# Sheet1.net
KiCad netlist of a schematic drawn in Altium Designer
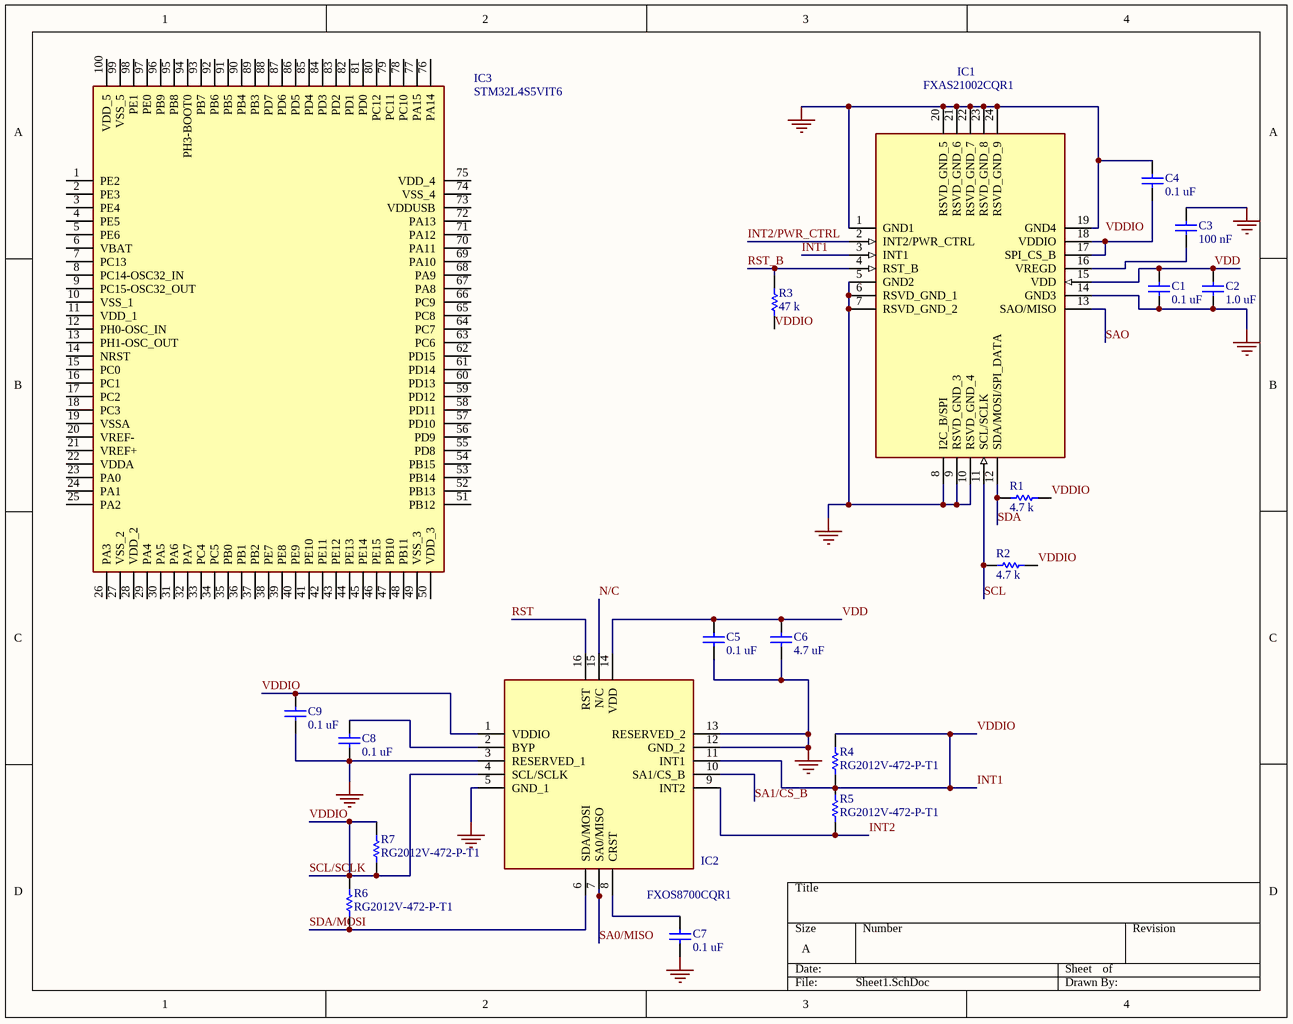
[diagram p0: Sheet1.SchDoc]

(export (version "E")
  (design (tool "Eeschema 10.0.6"))
  (components
    (comp (ref "C1")
      (value "0.1 uF")
      (footprint "CAPC1005X55X30ML05T10")
      (fields (field (name "MANUFACTURER") "Kemet") (field (name "PART NUMBER") "C0402C104J4RACTU"))
      (libsource (lib "Altium Content Vault") (part "CAP"))
    )
    (comp (ref "C2")
      (value "1.0 uF")
      (footprint "CAPC1005X55X30ML05T10")
      (fields (field (name "MANUFACTURER") "Kemet") (field (name "PART NUMBER") "C0402C104J4RACTU"))
      (libsource (lib "Altium Content Vault") (part "CAP"))
    )
    (comp (ref "C3")
      (value "100 nF")
      (footprint "CAPC1005X55X30ML05T10")
      (fields (field (name "MANUFACTURER") "Kemet") (field (name "PART NUMBER") "C0402C104J4RACTU"))
      (libsource (lib "Altium Content Vault") (part "CAP"))
    )
    (comp (ref "C4")
      (value "0.1 uF")
      (footprint "CAPC1005X55X30ML05T10")
      (fields (field (name "MANUFACTURER") "Kemet") (field (name "PART NUMBER") "C0402C104J4RACTU"))
      (libsource (lib "Altium Content Vault") (part "CAP"))
    )
    (comp (ref "C5")
      (value "0.1 uF")
      (footprint "CAPC1005X55X30ML05T10")
      (fields (field (name "MANUFACTURER") "Kemet") (field (name "PART NUMBER") "C0402C104J4RACTU"))
      (libsource (lib "Altium Content Vault") (part "CAP"))
    )
    (comp (ref "C6")
      (value "4.7 uF")
      (footprint "CAPC1005X55X30ML05T10")
      (fields (field (name "MANUFACTURER") "Kemet") (field (name "PART NUMBER") "C0402C104J4RACTU"))
      (libsource (lib "Altium Content Vault") (part "CAP"))
    )
    (comp (ref "C7")
      (value "0.1 uF")
      (footprint "CAPC1005X55X30ML05T10")
      (fields (field (name "MANUFACTURER") "Kemet") (field (name "PART NUMBER") "C0402C104J4RACTU"))
      (libsource (lib "Altium Content Vault") (part "CAP"))
    )
    (comp (ref "C8")
      (value "0.1 uF")
      (footprint "CAPC1005X55X30ML05T10")
      (fields (field (name "MANUFACTURER") "Kemet") (field (name "PART NUMBER") "C0402C104J4RACTU"))
      (libsource (lib "Altium Content Vault") (part "CAP"))
    )
    (comp (ref "C9")
      (value "0.1 uF")
      (footprint "CAPC1005X55X30ML05T10")
      (fields (field (name "MANUFACTURER") "Kemet") (field (name "PART NUMBER") "C0402C104J4RACTU"))
      (libsource (lib "Altium Content Vault") (part "CAP"))
    )
    (comp (ref "IC1")
      (value "FXAS21002CQR1")
      (footprint "SamacSys:FXAS21002CQR1")
      (description "Integrated Circuit")
      (fields (field (name "MOUSER PART NUMBER") "841-FXAS21002CQR1"))
      (libsource (lib "*") (part "FXAS21002CQR1"))
    )
    (comp (ref "IC2")
      (value "FXOS8700CQR1")
      (footprint "SamacSys:MMA8452QT")
      (description "Accelerometer")
      (fields (field (name "MOUSER PART NUMBER") "841-FXOS8700CQR1"))
      (libsource (lib "*") (part "FXOS8700CQR1"))
    )
    (comp (ref "IC3")
      (value "STM32L4S5VIT6")
      (footprint "SamacSys:QFP50P1600X1600X160-100N")
      (description "Integrated Circuit")
      (fields
        (field (name "MOUSER PART NUMBER") "511-STM32L4S5VIT6")
        (field (name "RS PART NUMBER") "1750803P")
      )
      (libsource (lib "*") (part "STM32L4S5VIT6"))
    )
    (comp (ref "R1")
      (value "4.7 k")
      (footprint "RESC2013X50X40LL20T20")
      (fields (field (name "PART NUMBER") "RG2012V-472-P-T1") (field (name "MANUFACTURER") "Susumu"))
      (libsource (lib "Altium Content Vault") (part "RES"))
    )
    (comp (ref "R2")
      (value "4.7 k")
      (footprint "RESC2013X50X40LL20T20")
      (fields (field (name "PART NUMBER") "RG2012V-472-P-T1") (field (name "MANUFACTURER") "Susumu"))
      (libsource (lib "Altium Content Vault") (part "RES"))
    )
    (comp (ref "R3")
      (value "47 k")
      (footprint "RESC2013X50X40ML20T20")
      (fields (field (name "PART NUMBER") "RG2012P-473-B-T5") (field (name "MANUFACTURER") "Susumu"))
      (libsource (lib "Altium Content Vault") (part "RES"))
    )
    (comp (ref "R4")
      (value "RG2012V-472-P-T1")
      (footprint "RESC2013X50X40LL20T20")
      (fields (field (name "MANUFACTURER") "Susumu"))
      (libsource (lib "Altium Content Vault") (part "RES"))
    )
    (comp (ref "R5")
      (value "RG2012V-472-P-T1")
      (footprint "RESC2013X50X40LL20T20")
      (fields (field (name "MANUFACTURER") "Susumu"))
      (libsource (lib "Altium Content Vault") (part "RES"))
    )
    (comp (ref "R6")
      (value "RG2012V-472-P-T1")
      (footprint "RESC2013X50X40LL20T20")
      (fields (field (name "MANUFACTURER") "Susumu"))
      (libsource (lib "Altium Content Vault") (part "RES"))
    )
    (comp (ref "R7")
      (value "RG2012V-472-P-T1")
      (footprint "RESC2013X50X40LL20T20")
      (fields (field (name "MANUFACTURER") "Susumu"))
      (libsource (lib "Altium Content Vault") (part "RES"))
    )
  )
  (nets
    (net (code "1") (name "/INT1") (class "Default")
      (node (ref "C9") (pin "2") (pinfunction "2_2") (pintype "passive"))
      (node (ref "IC1") (pin "3") (pinfunction "INT1_3") (pintype "input"))
      (node (ref "IC2") (pin "1") (pinfunction "VDDIO_1") (pintype "passive"))
      (node (ref "IC2") (pin "11") (pinfunction "INT1_11") (pintype "passive"))
      (node (ref "IC2") (pin "4") (pinfunction "SCL/SCLK_4") (pintype "passive"))
      (node (ref "R1") (pin "2") (pinfunction "2_2") (pintype "passive"))
      (node (ref "R2") (pin "2") (pinfunction "2_2") (pintype "passive"))
      (node (ref "R3") (pin "1") (pinfunction "1_1") (pintype "passive"))
      (node (ref "R4") (pin "1") (pinfunction "1_1") (pintype "passive"))
      (node (ref "R4") (pin "2") (pinfunction "2_2") (pintype "passive"))
      (node (ref "R6") (pin "2") (pinfunction "2_2") (pintype "passive"))
      (node (ref "R7") (pin "1") (pinfunction "1_1") (pintype "passive"))
      (node (ref "R7") (pin "2") (pinfunction "2_2") (pintype "passive"))
    )
    (net (code "2") (name "/INT2") (class "Default")
      (node (ref "IC2") (pin "9") (pinfunction "INT2_9") (pintype "passive"))
      (node (ref "R5") (pin "1") (pinfunction "1_1") (pintype "passive"))
    )
    (net (code "3") (name "/INT2{slash}PWR_CTRL") (class "Default")
      (node (ref "IC1") (pin "2") (pinfunction "INT2/PWR_CTRL_2") (pintype "input"))
    )
    (net (code "4") (name "/N{slash}C") (class "Default")
      (node (ref "IC2") (pin "15") (pinfunction "N/C_15") (pintype "passive"))
    )
    (net (code "5") (name "/RST") (class "Default")
      (node (ref "IC2") (pin "16") (pinfunction "RST_16") (pintype "passive"))
    )
    (net (code "6") (name "/RST_B") (class "Default")
      (node (ref "IC1") (pin "4") (pinfunction "RST_B_4") (pintype "input"))
      (node (ref "R3") (pin "2") (pinfunction "2_2") (pintype "passive"))
    )
    (net (code "7") (name "/SA0{slash}MISO") (class "Default")
      (node (ref "IC2") (pin "7") (pinfunction "SA0/MISO_7") (pintype "passive"))
    )
    (net (code "8") (name "/SA1{slash}CS_B") (class "Default")
      (node (ref "IC2") (pin "10") (pinfunction "SA1/CS_B_10") (pintype "passive"))
    )
    (net (code "9") (name "/SAO") (class "Default")
      (node (ref "IC1") (pin "13") (pinfunction "SAO/MISO_13") (pintype "power_in"))
    )
    (net (code "10") (name "/SCL") (class "Default")
      (node (ref "IC1") (pin "11") (pinfunction "SCL/SCLK_11") (pintype "input"))
      (node (ref "R2") (pin "1") (pinfunction "1_1") (pintype "passive"))
    )
    (net (code "11") (name "/SDA") (class "Default")
      (node (ref "IC1") (pin "12") (pinfunction "SDA/MOSI/SPI_DATA_12") (pintype "passive"))
      (node (ref "R1") (pin "1") (pinfunction "1_1") (pintype "passive"))
    )
    (net (code "12") (name "/SDA{slash}MOSI") (class "Default")
      (node (ref "IC2") (pin "6") (pinfunction "SDA/MOSI_6") (pintype "passive"))
      (node (ref "R6") (pin "1") (pinfunction "1_1") (pintype "passive"))
    )
    (net (code "13") (name "/VDD") (class "Default")
      (node (ref "C1") (pin "2") (pinfunction "2_2") (pintype "passive"))
      (node (ref "C2") (pin "2") (pinfunction "2_2") (pintype "passive"))
      (node (ref "C5") (pin "2") (pinfunction "2_2") (pintype "passive"))
      (node (ref "C6") (pin "2") (pinfunction "2_2") (pintype "passive"))
      (node (ref "IC1") (pin "15") (pinfunction "VDD_15") (pintype "input"))
      (node (ref "IC2") (pin "14") (pinfunction "VDD_14") (pintype "passive"))
    )
    (net (code "14") (name "GND") (class "Default")
      (node (ref "C1") (pin "1") (pinfunction "1_1") (pintype "passive"))
      (node (ref "C2") (pin "1") (pinfunction "1_1") (pintype "passive"))
      (node (ref "C3") (pin "2") (pinfunction "2_2") (pintype "passive"))
      (node (ref "C4") (pin "1") (pinfunction "1_1") (pintype "passive"))
      (node (ref "C5") (pin "1") (pinfunction "1_1") (pintype "passive"))
      (node (ref "C6") (pin "1") (pinfunction "1_1") (pintype "passive"))
      (node (ref "C7") (pin "1") (pinfunction "1_1") (pintype "passive"))
      (node (ref "C8") (pin "1") (pinfunction "1_1") (pintype "passive"))
      (node (ref "C9") (pin "1") (pinfunction "1_1") (pintype "passive"))
      (node (ref "IC1") (pin "1") (pinfunction "GND1_1") (pintype "power_in"))
      (node (ref "IC1") (pin "10") (pinfunction "RSVD_GND_4_10") (pintype "power_in"))
      (node (ref "IC1") (pin "14") (pinfunction "GND3_14") (pintype "power_in"))
      (node (ref "IC1") (pin "19") (pinfunction "GND4_19") (pintype "passive"))
      (node (ref "IC1") (pin "20") (pinfunction "RSVD_GND_5_20") (pintype "power_in"))
      (node (ref "IC1") (pin "21") (pinfunction "RSVD_GND_6_21") (pintype "power_in"))
      (node (ref "IC1") (pin "22") (pinfunction "RSVD_GND_7_22") (pintype "power_in"))
      (node (ref "IC1") (pin "23") (pinfunction "RSVD_GND_8_23") (pintype "power_in"))
      (node (ref "IC1") (pin "24") (pinfunction "RSVD_GND_9_24") (pintype "power_in"))
      (node (ref "IC1") (pin "5") (pinfunction "GND2_5") (pintype "power_in"))
      (node (ref "IC1") (pin "6") (pinfunction "RSVD_GND_1_6") (pintype "power_in"))
      (node (ref "IC1") (pin "7") (pinfunction "RSVD_GND_2_7") (pintype "power_in"))
      (node (ref "IC1") (pin "8") (pinfunction "I2C_B/SPI_8") (pintype "passive"))
      (node (ref "IC1") (pin "9") (pinfunction "RSVD_GND_3_9") (pintype "power_in"))
      (node (ref "IC2") (pin "12") (pinfunction "GND_2_12") (pintype "passive"))
      (node (ref "IC2") (pin "13") (pinfunction "RESERVED_2_13") (pintype "passive"))
      (node (ref "IC2") (pin "3") (pinfunction "RESERVED_1_3") (pintype "passive"))
      (node (ref "IC2") (pin "5") (pinfunction "GND_1_5") (pintype "passive"))
    )
    (net (code "15") (name "Net-(IC1-SPI_CS_B)") (class "Default")
      (node (ref "C4") (pin "2") (pinfunction "2_2") (pintype "passive"))
      (node (ref "IC1") (pin "17") (pinfunction "SPI_CS_B_17") (pintype "power_in"))
      (node (ref "IC1") (pin "18") (pinfunction "VDDIO_18") (pintype "power_in"))
    )
    (net (code "16") (name "Net-(IC1-VREGD)") (class "Default")
      (node (ref "C3") (pin "1") (pinfunction "1_1") (pintype "passive"))
      (node (ref "IC1") (pin "16") (pinfunction "VREGD_16") (pintype "passive"))
    )
    (net (code "17") (name "Net-(IC2-BYP)") (class "Default")
      (node (ref "C8") (pin "2") (pinfunction "2_2") (pintype "passive"))
      (node (ref "IC2") (pin "2") (pinfunction "BYP_2") (pintype "passive"))
    )
    (net (code "18") (name "Net-(IC2-CRST)") (class "Default")
      (node (ref "C7") (pin "2") (pinfunction "2_2") (pintype "passive"))
      (node (ref "IC2") (pin "8") (pinfunction "CRST_8") (pintype "passive"))
    )
    (net (code "19") (name "unconnected-(IC3-NRST-Pad14)") (class "Default")
      (node (ref "IC3") (pin "14") (pinfunction "NRST_14") (pintype "passive"))
    )
    (net (code "20") (name "unconnected-(IC3-PA0-Pad23)") (class "Default")
      (node (ref "IC3") (pin "23") (pinfunction "PA0_23") (pintype "passive"))
    )
    (net (code "21") (name "unconnected-(IC3-PA1-Pad24)") (class "Default")
      (node (ref "IC3") (pin "24") (pinfunction "PA1_24") (pintype "passive"))
    )
    (net (code "22") (name "unconnected-(IC3-PA2-Pad25)") (class "Default")
      (node (ref "IC3") (pin "25") (pinfunction "PA2_25") (pintype "passive"))
    )
    (net (code "23") (name "unconnected-(IC3-PA3-Pad26)") (class "Default")
      (node (ref "IC3") (pin "26") (pinfunction "PA3_26") (pintype "passive"))
    )
    (net (code "24") (name "unconnected-(IC3-PA4-Pad29)") (class "Default")
      (node (ref "IC3") (pin "29") (pinfunction "PA4_29") (pintype "passive"))
    )
    (net (code "25") (name "unconnected-(IC3-PA5-Pad30)") (class "Default")
      (node (ref "IC3") (pin "30") (pinfunction "PA5_30") (pintype "passive"))
    )
    (net (code "26") (name "unconnected-(IC3-PA6-Pad31)") (class "Default")
      (node (ref "IC3") (pin "31") (pinfunction "PA6_31") (pintype "passive"))
    )
    (net (code "27") (name "unconnected-(IC3-PA7-Pad32)") (class "Default")
      (node (ref "IC3") (pin "32") (pinfunction "PA7_32") (pintype "passive"))
    )
    (net (code "28") (name "unconnected-(IC3-PA8-Pad67)") (class "Default")
      (node (ref "IC3") (pin "67") (pinfunction "PA8_67") (pintype "passive"))
    )
    (net (code "29") (name "unconnected-(IC3-PA9-Pad68)") (class "Default")
      (node (ref "IC3") (pin "68") (pinfunction "PA9_68") (pintype "passive"))
    )
    (net (code "30") (name "unconnected-(IC3-PA10-Pad69)") (class "Default")
      (node (ref "IC3") (pin "69") (pinfunction "PA10_69") (pintype "passive"))
    )
    (net (code "31") (name "unconnected-(IC3-PA11-Pad70)") (class "Default")
      (node (ref "IC3") (pin "70") (pinfunction "PA11_70") (pintype "passive"))
    )
    (net (code "32") (name "unconnected-(IC3-PA12-Pad71)") (class "Default")
      (node (ref "IC3") (pin "71") (pinfunction "PA12_71") (pintype "passive"))
    )
    (net (code "33") (name "unconnected-(IC3-PA13-Pad72)") (class "Default")
      (node (ref "IC3") (pin "72") (pinfunction "PA13_72") (pintype "passive"))
    )
    (net (code "34") (name "unconnected-(IC3-PA14-Pad76)") (class "Default")
      (node (ref "IC3") (pin "76") (pinfunction "PA14_76") (pintype "passive"))
    )
    (net (code "35") (name "unconnected-(IC3-PA15-Pad77)") (class "Default")
      (node (ref "IC3") (pin "77") (pinfunction "PA15_77") (pintype "passive"))
    )
    (net (code "36") (name "unconnected-(IC3-PB0-Pad35)") (class "Default")
      (node (ref "IC3") (pin "35") (pinfunction "PB0_35") (pintype "passive"))
    )
    (net (code "37") (name "unconnected-(IC3-PB1-Pad36)") (class "Default")
      (node (ref "IC3") (pin "36") (pinfunction "PB1_36") (pintype "passive"))
    )
    (net (code "38") (name "unconnected-(IC3-PB2-Pad37)") (class "Default")
      (node (ref "IC3") (pin "37") (pinfunction "PB2_37") (pintype "passive"))
    )
    (net (code "39") (name "unconnected-(IC3-PB3-Pad89)") (class "Default")
      (node (ref "IC3") (pin "89") (pinfunction "PB3_89") (pintype "passive"))
    )
    (net (code "40") (name "unconnected-(IC3-PB4-Pad90)") (class "Default")
      (node (ref "IC3") (pin "90") (pinfunction "PB4_90") (pintype "passive"))
    )
    (net (code "41") (name "unconnected-(IC3-PB5-Pad91)") (class "Default")
      (node (ref "IC3") (pin "91") (pinfunction "PB5_91") (pintype "passive"))
    )
    (net (code "42") (name "unconnected-(IC3-PB6-Pad92)") (class "Default")
      (node (ref "IC3") (pin "92") (pinfunction "PB6_92") (pintype "passive"))
    )
    (net (code "43") (name "unconnected-(IC3-PB7-Pad93)") (class "Default")
      (node (ref "IC3") (pin "93") (pinfunction "PB7_93") (pintype "passive"))
    )
    (net (code "44") (name "unconnected-(IC3-PB8-Pad95)") (class "Default")
      (node (ref "IC3") (pin "95") (pinfunction "PB8_95") (pintype "passive"))
    )
    (net (code "45") (name "unconnected-(IC3-PB9-Pad96)") (class "Default")
      (node (ref "IC3") (pin "96") (pinfunction "PB9_96") (pintype "passive"))
    )
    (net (code "46") (name "unconnected-(IC3-PB10-Pad47)") (class "Default")
      (node (ref "IC3") (pin "47") (pinfunction "PB10_47") (pintype "passive"))
    )
    (net (code "47") (name "unconnected-(IC3-PB11-Pad48)") (class "Default")
      (node (ref "IC3") (pin "48") (pinfunction "PB11_48") (pintype "passive"))
    )
    (net (code "48") (name "unconnected-(IC3-PB12-Pad51)") (class "Default")
      (node (ref "IC3") (pin "51") (pinfunction "PB12_51") (pintype "passive"))
    )
    (net (code "49") (name "unconnected-(IC3-PB13-Pad52)") (class "Default")
      (node (ref "IC3") (pin "52") (pinfunction "PB13_52") (pintype "passive"))
    )
    (net (code "50") (name "unconnected-(IC3-PB14-Pad53)") (class "Default")
      (node (ref "IC3") (pin "53") (pinfunction "PB14_53") (pintype "passive"))
    )
    (net (code "51") (name "unconnected-(IC3-PB15-Pad54)") (class "Default")
      (node (ref "IC3") (pin "54") (pinfunction "PB15_54") (pintype "passive"))
    )
    (net (code "52") (name "unconnected-(IC3-PC0-Pad15)") (class "Default")
      (node (ref "IC3") (pin "15") (pinfunction "PC0_15") (pintype "passive"))
    )
    (net (code "53") (name "unconnected-(IC3-PC1-Pad16)") (class "Default")
      (node (ref "IC3") (pin "16") (pinfunction "PC1_16") (pintype "passive"))
    )
    (net (code "54") (name "unconnected-(IC3-PC2-Pad17)") (class "Default")
      (node (ref "IC3") (pin "17") (pinfunction "PC2_17") (pintype "passive"))
    )
    (net (code "55") (name "unconnected-(IC3-PC3-Pad18)") (class "Default")
      (node (ref "IC3") (pin "18") (pinfunction "PC3_18") (pintype "passive"))
    )
    (net (code "56") (name "unconnected-(IC3-PC4-Pad33)") (class "Default")
      (node (ref "IC3") (pin "33") (pinfunction "PC4_33") (pintype "passive"))
    )
    (net (code "57") (name "unconnected-(IC3-PC5-Pad34)") (class "Default")
      (node (ref "IC3") (pin "34") (pinfunction "PC5_34") (pintype "passive"))
    )
    (net (code "58") (name "unconnected-(IC3-PC6-Pad63)") (class "Default")
      (node (ref "IC3") (pin "63") (pinfunction "PC6_63") (pintype "passive"))
    )
    (net (code "59") (name "unconnected-(IC3-PC7-Pad64)") (class "Default")
      (node (ref "IC3") (pin "64") (pinfunction "PC7_64") (pintype "passive"))
    )
    (net (code "60") (name "unconnected-(IC3-PC8-Pad65)") (class "Default")
      (node (ref "IC3") (pin "65") (pinfunction "PC8_65") (pintype "passive"))
    )
    (net (code "61") (name "unconnected-(IC3-PC9-Pad66)") (class "Default")
      (node (ref "IC3") (pin "66") (pinfunction "PC9_66") (pintype "passive"))
    )
    (net (code "62") (name "unconnected-(IC3-PC10-Pad78)") (class "Default")
      (node (ref "IC3") (pin "78") (pinfunction "PC10_78") (pintype "passive"))
    )
    (net (code "63") (name "unconnected-(IC3-PC11-Pad79)") (class "Default")
      (node (ref "IC3") (pin "79") (pinfunction "PC11_79") (pintype "passive"))
    )
    (net (code "64") (name "unconnected-(IC3-PC12-Pad80)") (class "Default")
      (node (ref "IC3") (pin "80") (pinfunction "PC12_80") (pintype "passive"))
    )
    (net (code "65") (name "unconnected-(IC3-PC13-Pad7)") (class "Default")
      (node (ref "IC3") (pin "7") (pinfunction "PC13_7") (pintype "passive"))
    )
    (net (code "66") (name "unconnected-(IC3-PC14-OSC32_IN-Pad8)") (class "Default")
      (node (ref "IC3") (pin "8") (pinfunction "PC14-OSC32_IN_8") (pintype "passive"))
    )
    (net (code "67") (name "unconnected-(IC3-PC15-OSC32_OUT-Pad9)") (class "Default")
      (node (ref "IC3") (pin "9") (pinfunction "PC15-OSC32_OUT_9") (pintype "passive"))
    )
    (net (code "68") (name "unconnected-(IC3-PD0-Pad81)") (class "Default")
      (node (ref "IC3") (pin "81") (pinfunction "PD0_81") (pintype "passive"))
    )
    (net (code "69") (name "unconnected-(IC3-PD1-Pad82)") (class "Default")
      (node (ref "IC3") (pin "82") (pinfunction "PD1_82") (pintype "passive"))
    )
    (net (code "70") (name "unconnected-(IC3-PD2-Pad83)") (class "Default")
      (node (ref "IC3") (pin "83") (pinfunction "PD2_83") (pintype "passive"))
    )
    (net (code "71") (name "unconnected-(IC3-PD3-Pad84)") (class "Default")
      (node (ref "IC3") (pin "84") (pinfunction "PD3_84") (pintype "passive"))
    )
    (net (code "72") (name "unconnected-(IC3-PD4-Pad85)") (class "Default")
      (node (ref "IC3") (pin "85") (pinfunction "PD4_85") (pintype "passive"))
    )
    (net (code "73") (name "unconnected-(IC3-PD5-Pad86)") (class "Default")
      (node (ref "IC3") (pin "86") (pinfunction "PD5_86") (pintype "passive"))
    )
    (net (code "74") (name "unconnected-(IC3-PD6-Pad87)") (class "Default")
      (node (ref "IC3") (pin "87") (pinfunction "PD6_87") (pintype "passive"))
    )
    (net (code "75") (name "unconnected-(IC3-PD7-Pad88)") (class "Default")
      (node (ref "IC3") (pin "88") (pinfunction "PD7_88") (pintype "passive"))
    )
    (net (code "76") (name "unconnected-(IC3-PD8-Pad55)") (class "Default")
      (node (ref "IC3") (pin "55") (pinfunction "PD8_55") (pintype "passive"))
    )
    (net (code "77") (name "unconnected-(IC3-PD9-Pad56)") (class "Default")
      (node (ref "IC3") (pin "56") (pinfunction "PD9_56") (pintype "passive"))
    )
    (net (code "78") (name "unconnected-(IC3-PD10-Pad57)") (class "Default")
      (node (ref "IC3") (pin "57") (pinfunction "PD10_57") (pintype "passive"))
    )
    (net (code "79") (name "unconnected-(IC3-PD11-Pad58)") (class "Default")
      (node (ref "IC3") (pin "58") (pinfunction "PD11_58") (pintype "passive"))
    )
    (net (code "80") (name "unconnected-(IC3-PD12-Pad59)") (class "Default")
      (node (ref "IC3") (pin "59") (pinfunction "PD12_59") (pintype "passive"))
    )
    (net (code "81") (name "unconnected-(IC3-PD13-Pad60)") (class "Default")
      (node (ref "IC3") (pin "60") (pinfunction "PD13_60") (pintype "passive"))
    )
    (net (code "82") (name "unconnected-(IC3-PD14-Pad61)") (class "Default")
      (node (ref "IC3") (pin "61") (pinfunction "PD14_61") (pintype "passive"))
    )
    (net (code "83") (name "unconnected-(IC3-PD15-Pad62)") (class "Default")
      (node (ref "IC3") (pin "62") (pinfunction "PD15_62") (pintype "passive"))
    )
    (net (code "84") (name "unconnected-(IC3-PE0-Pad97)") (class "Default")
      (node (ref "IC3") (pin "97") (pinfunction "PE0_97") (pintype "passive"))
    )
    (net (code "85") (name "unconnected-(IC3-PE1-Pad98)") (class "Default")
      (node (ref "IC3") (pin "98") (pinfunction "PE1_98") (pintype "passive"))
    )
    (net (code "86") (name "unconnected-(IC3-PE2-Pad1)") (class "Default")
      (node (ref "IC3") (pin "1") (pinfunction "PE2_1") (pintype "passive"))
    )
    (net (code "87") (name "unconnected-(IC3-PE3-Pad2)") (class "Default")
      (node (ref "IC3") (pin "2") (pinfunction "PE3_2") (pintype "passive"))
    )
    (net (code "88") (name "unconnected-(IC3-PE4-Pad3)") (class "Default")
      (node (ref "IC3") (pin "3") (pinfunction "PE4_3") (pintype "passive"))
    )
    (net (code "89") (name "unconnected-(IC3-PE5-Pad4)") (class "Default")
      (node (ref "IC3") (pin "4") (pinfunction "PE5_4") (pintype "passive"))
    )
    (net (code "90") (name "unconnected-(IC3-PE6-Pad5)") (class "Default")
      (node (ref "IC3") (pin "5") (pinfunction "PE6_5") (pintype "passive"))
    )
    (net (code "91") (name "unconnected-(IC3-PE7-Pad38)") (class "Default")
      (node (ref "IC3") (pin "38") (pinfunction "PE7_38") (pintype "passive"))
    )
    (net (code "92") (name "unconnected-(IC3-PE8-Pad39)") (class "Default")
      (node (ref "IC3") (pin "39") (pinfunction "PE8_39") (pintype "passive"))
    )
    (net (code "93") (name "unconnected-(IC3-PE9-Pad40)") (class "Default")
      (node (ref "IC3") (pin "40") (pinfunction "PE9_40") (pintype "passive"))
    )
    (net (code "94") (name "unconnected-(IC3-PE10-Pad41)") (class "Default")
      (node (ref "IC3") (pin "41") (pinfunction "PE10_41") (pintype "passive"))
    )
    (net (code "95") (name "unconnected-(IC3-PE11-Pad42)") (class "Default")
      (node (ref "IC3") (pin "42") (pinfunction "PE11_42") (pintype "passive"))
    )
    (net (code "96") (name "unconnected-(IC3-PE12-Pad43)") (class "Default")
      (node (ref "IC3") (pin "43") (pinfunction "PE12_43") (pintype "passive"))
    )
    (net (code "97") (name "unconnected-(IC3-PE13-Pad44)") (class "Default")
      (node (ref "IC3") (pin "44") (pinfunction "PE13_44") (pintype "passive"))
    )
    (net (code "98") (name "unconnected-(IC3-PE14-Pad45)") (class "Default")
      (node (ref "IC3") (pin "45") (pinfunction "PE14_45") (pintype "passive"))
    )
    (net (code "99") (name "unconnected-(IC3-PE15-Pad46)") (class "Default")
      (node (ref "IC3") (pin "46") (pinfunction "PE15_46") (pintype "passive"))
    )
    (net (code "100") (name "unconnected-(IC3-PH0-OSC_IN-Pad12)") (class "Default")
      (node (ref "IC3") (pin "12") (pinfunction "PH0-OSC_IN_12") (pintype "passive"))
    )
    (net (code "101") (name "unconnected-(IC3-PH1-OSC_OUT-Pad13)") (class "Default")
      (node (ref "IC3") (pin "13") (pinfunction "PH1-OSC_OUT_13") (pintype "passive"))
    )
    (net (code "102") (name "unconnected-(IC3-PH3-BOOT0-Pad94)") (class "Default")
      (node (ref "IC3") (pin "94") (pinfunction "PH3-BOOT0_94") (pintype "passive"))
    )
    (net (code "103") (name "unconnected-(IC3-VBAT-Pad6)") (class "Default")
      (node (ref "IC3") (pin "6") (pinfunction "VBAT_6") (pintype "passive"))
    )
    (net (code "104") (name "unconnected-(IC3-VDDA-Pad22)") (class "Default")
      (node (ref "IC3") (pin "22") (pinfunction "VDDA_22") (pintype "passive"))
    )
    (net (code "105") (name "unconnected-(IC3-VDDUSB-Pad73)") (class "Default")
      (node (ref "IC3") (pin "73") (pinfunction "VDDUSB_73") (pintype "passive"))
    )
    (net (code "106") (name "unconnected-(IC3-VDD_1-Pad11)") (class "Default")
      (node (ref "IC3") (pin "11") (pinfunction "VDD_1_11") (pintype "passive"))
    )
    (net (code "107") (name "unconnected-(IC3-VDD_2-Pad28)") (class "Default")
      (node (ref "IC3") (pin "28") (pinfunction "VDD_2_28") (pintype "passive"))
    )
    (net (code "108") (name "unconnected-(IC3-VDD_3-Pad50)") (class "Default")
      (node (ref "IC3") (pin "50") (pinfunction "VDD_3_50") (pintype "passive"))
    )
    (net (code "109") (name "unconnected-(IC3-VDD_4-Pad75)") (class "Default")
      (node (ref "IC3") (pin "75") (pinfunction "VDD_4_75") (pintype "passive"))
    )
    (net (code "110") (name "unconnected-(IC3-VDD_5-Pad100)") (class "Default")
      (node (ref "IC3") (pin "100") (pinfunction "VDD_5_100") (pintype "passive"))
    )
    (net (code "111") (name "unconnected-(IC3-VREF+-Pad21)") (class "Default")
      (node (ref "IC3") (pin "21") (pinfunction "VREF+_21") (pintype "passive"))
    )
    (net (code "112") (name "unconnected-(IC3-VREF--Pad20)") (class "Default")
      (node (ref "IC3") (pin "20") (pinfunction "VREF-_20") (pintype "passive"))
    )
    (net (code "113") (name "unconnected-(IC3-VSSA-Pad19)") (class "Default")
      (node (ref "IC3") (pin "19") (pinfunction "VSSA_19") (pintype "passive"))
    )
    (net (code "114") (name "unconnected-(IC3-VSS_1-Pad10)") (class "Default")
      (node (ref "IC3") (pin "10") (pinfunction "VSS_1_10") (pintype "passive"))
    )
    (net (code "115") (name "unconnected-(IC3-VSS_2-Pad27)") (class "Default")
      (node (ref "IC3") (pin "27") (pinfunction "VSS_2_27") (pintype "passive"))
    )
    (net (code "116") (name "unconnected-(IC3-VSS_3-Pad49)") (class "Default")
      (node (ref "IC3") (pin "49") (pinfunction "VSS_3_49") (pintype "passive"))
    )
    (net (code "117") (name "unconnected-(IC3-VSS_4-Pad74)") (class "Default")
      (node (ref "IC3") (pin "74") (pinfunction "VSS_4_74") (pintype "passive"))
    )
    (net (code "118") (name "unconnected-(IC3-VSS_5-Pad99)") (class "Default")
      (node (ref "IC3") (pin "99") (pinfunction "VSS_5_99") (pintype "passive"))
    )
    (net (code "119") (name "unconnected-(R5-Pad2)") (class "Default")
      (node (ref "R5") (pin "2") (pinfunction "2_2") (pintype "passive"))
    )
  )
)
